# led_balloon_v28.net
KiCad netlist of a schematic drawn in EAGLE
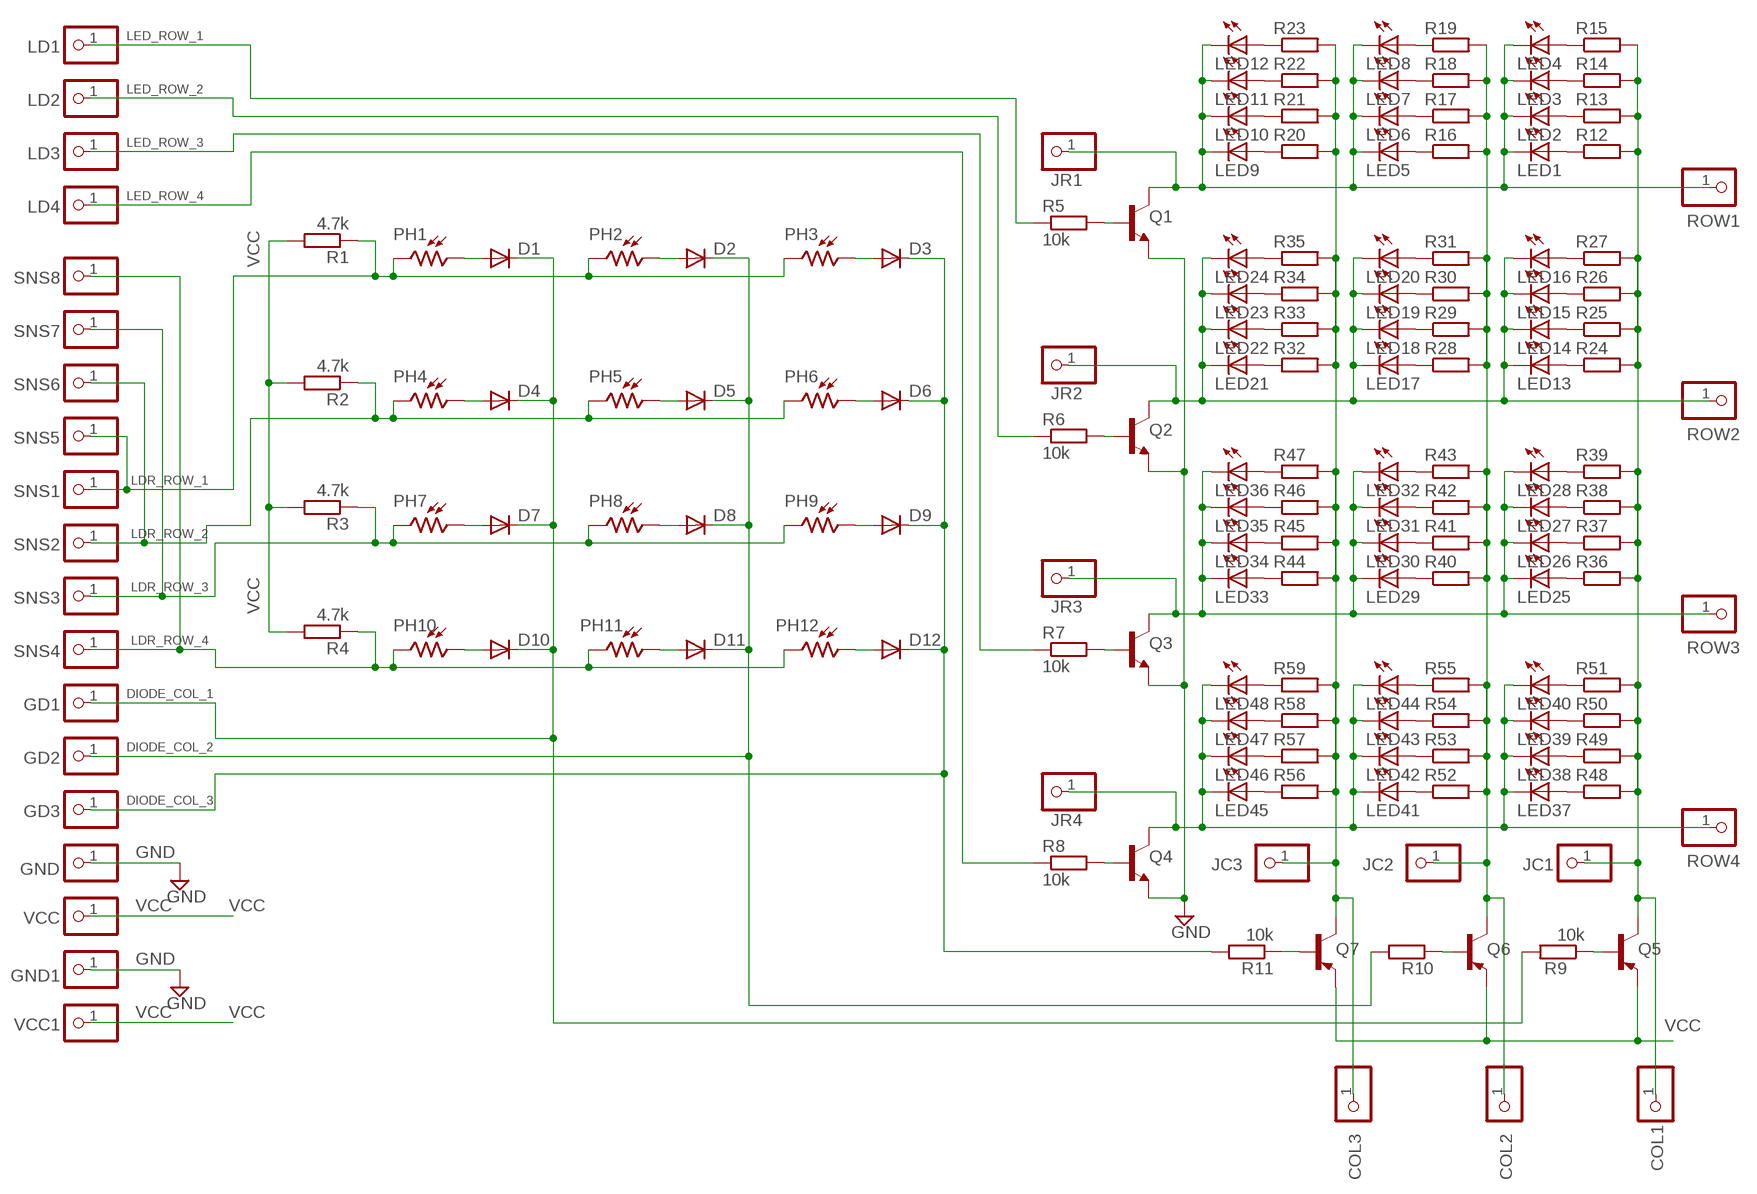
[diagram p0: schematic, sheet 1]

(export (version "E")
  (design (tool "Eeschema 10.0.6"))
  (components
    (comp (ref "COL1")
      (value "PINHD-1X1")
      (footprint "eagle-import:1X01")
      (libsource (lib "eagle-import") (part "PINHD-1X1"))
    )
    (comp (ref "COL2")
      (value "PINHD-1X1")
      (footprint "eagle-import:1X01")
      (libsource (lib "eagle-import") (part "PINHD-1X1"))
    )
    (comp (ref "COL3")
      (value "PINHD-1X1")
      (footprint "eagle-import:1X01")
      (libsource (lib "eagle-import") (part "PINHD-1X1"))
    )
    (comp (ref "D1")
      (value "1N4148DO35-7")
      (footprint "eagle-import:DO35-7")
      (libsource (lib "eagle-import") (part "1N4148DO35-7"))
    )
    (comp (ref "D2")
      (value "1N4148DO35-7")
      (footprint "eagle-import:DO35-7")
      (libsource (lib "eagle-import") (part "1N4148DO35-7"))
    )
    (comp (ref "D3")
      (value "1N4148DO35-7")
      (footprint "eagle-import:DO35-7")
      (libsource (lib "eagle-import") (part "1N4148DO35-7"))
    )
    (comp (ref "D4")
      (value "1N4148DO35-7")
      (footprint "eagle-import:DO35-7")
      (libsource (lib "eagle-import") (part "1N4148DO35-7"))
    )
    (comp (ref "D5")
      (value "1N4148DO35-7")
      (footprint "eagle-import:DO35-7")
      (libsource (lib "eagle-import") (part "1N4148DO35-7"))
    )
    (comp (ref "D6")
      (value "1N4148DO35-7")
      (footprint "eagle-import:DO35-7")
      (libsource (lib "eagle-import") (part "1N4148DO35-7"))
    )
    (comp (ref "D7")
      (value "1N4148DO35-7")
      (footprint "eagle-import:DO35-7")
      (libsource (lib "eagle-import") (part "1N4148DO35-7"))
    )
    (comp (ref "D8")
      (value "1N4148DO35-7")
      (footprint "eagle-import:DO35-7")
      (libsource (lib "eagle-import") (part "1N4148DO35-7"))
    )
    (comp (ref "D9")
      (value "1N4148DO35-7")
      (footprint "eagle-import:DO35-7")
      (libsource (lib "eagle-import") (part "1N4148DO35-7"))
    )
    (comp (ref "D10")
      (value "1N4148DO35-7")
      (footprint "eagle-import:DO35-7")
      (libsource (lib "eagle-import") (part "1N4148DO35-7"))
    )
    (comp (ref "D11")
      (value "1N4148DO35-7")
      (footprint "eagle-import:DO35-7")
      (libsource (lib "eagle-import") (part "1N4148DO35-7"))
    )
    (comp (ref "D12")
      (value "1N4148DO35-7")
      (footprint "eagle-import:DO35-7")
      (libsource (lib "eagle-import") (part "1N4148DO35-7"))
    )
    (comp (ref "GD1")
      (value "PINHD-1X1")
      (footprint "eagle-import:1X01")
      (libsource (lib "eagle-import") (part "PINHD-1X1"))
    )
    (comp (ref "GD2")
      (value "PINHD-1X1")
      (footprint "eagle-import:1X01")
      (libsource (lib "eagle-import") (part "PINHD-1X1"))
    )
    (comp (ref "GD3")
      (value "PINHD-1X1")
      (footprint "eagle-import:1X01")
      (libsource (lib "eagle-import") (part "PINHD-1X1"))
    )
    (comp (ref "GND")
      (value "PINHD-1X1")
      (footprint "eagle-import:1X01")
      (libsource (lib "eagle-import") (part "PINHD-1X1"))
    )
    (comp (ref "GND1")
      (value "PINHD-1X1")
      (footprint "eagle-import:1X01")
      (libsource (lib "eagle-import") (part "PINHD-1X1"))
    )
    (comp (ref "JC1")
      (value "PINHD-1X1")
      (footprint "eagle-import:1X01")
      (libsource (lib "eagle-import") (part "PINHD-1X1"))
    )
    (comp (ref "JC2")
      (value "PINHD-1X1")
      (footprint "eagle-import:1X01")
      (libsource (lib "eagle-import") (part "PINHD-1X1"))
    )
    (comp (ref "JC3")
      (value "PINHD-1X1")
      (footprint "eagle-import:1X01")
      (libsource (lib "eagle-import") (part "PINHD-1X1"))
    )
    (comp (ref "JR1")
      (value "PINHD-1X1")
      (footprint "eagle-import:1X01")
      (libsource (lib "eagle-import") (part "PINHD-1X1"))
    )
    (comp (ref "JR2")
      (value "PINHD-1X1")
      (footprint "eagle-import:1X01")
      (libsource (lib "eagle-import") (part "PINHD-1X1"))
    )
    (comp (ref "JR3")
      (value "PINHD-1X1")
      (footprint "eagle-import:1X01")
      (libsource (lib "eagle-import") (part "PINHD-1X1"))
    )
    (comp (ref "JR4")
      (value "PINHD-1X1")
      (footprint "eagle-import:1X01")
      (libsource (lib "eagle-import") (part "PINHD-1X1"))
    )
    (comp (ref "LD1")
      (value "PINHD-1X1")
      (footprint "eagle-import:1X01")
      (libsource (lib "eagle-import") (part "PINHD-1X1"))
    )
    (comp (ref "LD2")
      (value "PINHD-1X1")
      (footprint "eagle-import:1X01")
      (libsource (lib "eagle-import") (part "PINHD-1X1"))
    )
    (comp (ref "LD3")
      (value "PINHD-1X1")
      (footprint "eagle-import:1X01")
      (libsource (lib "eagle-import") (part "PINHD-1X1"))
    )
    (comp (ref "LD4")
      (value "PINHD-1X1")
      (footprint "eagle-import:1X01")
      (libsource (lib "eagle-import") (part "PINHD-1X1"))
    )
    (comp (ref "LED1")
      (value "LED3MM")
      (footprint "eagle-import:LED3MM")
      (libsource (lib "eagle-import") (part "LED3MM"))
    )
    (comp (ref "LED2")
      (value "LED3MM")
      (footprint "eagle-import:LED3MM")
      (libsource (lib "eagle-import") (part "LED3MM"))
    )
    (comp (ref "LED3")
      (value "LED3MM")
      (footprint "eagle-import:LED3MM")
      (libsource (lib "eagle-import") (part "LED3MM"))
    )
    (comp (ref "LED4")
      (value "LED3MM")
      (footprint "eagle-import:LED3MM")
      (libsource (lib "eagle-import") (part "LED3MM"))
    )
    (comp (ref "LED5")
      (value "LED3MM")
      (footprint "eagle-import:LED3MM")
      (libsource (lib "eagle-import") (part "LED3MM"))
    )
    (comp (ref "LED6")
      (value "LED3MM")
      (footprint "eagle-import:LED3MM")
      (libsource (lib "eagle-import") (part "LED3MM"))
    )
    (comp (ref "LED7")
      (value "LED3MM")
      (footprint "eagle-import:LED3MM")
      (libsource (lib "eagle-import") (part "LED3MM"))
    )
    (comp (ref "LED8")
      (value "LED3MM")
      (footprint "eagle-import:LED3MM")
      (libsource (lib "eagle-import") (part "LED3MM"))
    )
    (comp (ref "LED9")
      (value "LED3MM")
      (footprint "eagle-import:LED3MM")
      (libsource (lib "eagle-import") (part "LED3MM"))
    )
    (comp (ref "LED10")
      (value "LED3MM")
      (footprint "eagle-import:LED3MM")
      (libsource (lib "eagle-import") (part "LED3MM"))
    )
    (comp (ref "LED11")
      (value "LED3MM")
      (footprint "eagle-import:LED3MM")
      (libsource (lib "eagle-import") (part "LED3MM"))
    )
    (comp (ref "LED12")
      (value "LED3MM")
      (footprint "eagle-import:LED3MM")
      (libsource (lib "eagle-import") (part "LED3MM"))
    )
    (comp (ref "LED13")
      (value "LED3MM")
      (footprint "eagle-import:LED3MM")
      (libsource (lib "eagle-import") (part "LED3MM"))
    )
    (comp (ref "LED14")
      (value "LED3MM")
      (footprint "eagle-import:LED3MM")
      (libsource (lib "eagle-import") (part "LED3MM"))
    )
    (comp (ref "LED15")
      (value "LED3MM")
      (footprint "eagle-import:LED3MM")
      (libsource (lib "eagle-import") (part "LED3MM"))
    )
    (comp (ref "LED16")
      (value "LED3MM")
      (footprint "eagle-import:LED3MM")
      (libsource (lib "eagle-import") (part "LED3MM"))
    )
    (comp (ref "LED17")
      (value "LED3MM")
      (footprint "eagle-import:LED3MM")
      (libsource (lib "eagle-import") (part "LED3MM"))
    )
    (comp (ref "LED18")
      (value "LED3MM")
      (footprint "eagle-import:LED3MM")
      (libsource (lib "eagle-import") (part "LED3MM"))
    )
    (comp (ref "LED19")
      (value "LED3MM")
      (footprint "eagle-import:LED3MM")
      (libsource (lib "eagle-import") (part "LED3MM"))
    )
    (comp (ref "LED20")
      (value "LED3MM")
      (footprint "eagle-import:LED3MM")
      (libsource (lib "eagle-import") (part "LED3MM"))
    )
    (comp (ref "LED21")
      (value "LED3MM")
      (footprint "eagle-import:LED3MM")
      (libsource (lib "eagle-import") (part "LED3MM"))
    )
    (comp (ref "LED22")
      (value "LED3MM")
      (footprint "eagle-import:LED3MM")
      (libsource (lib "eagle-import") (part "LED3MM"))
    )
    (comp (ref "LED23")
      (value "LED3MM")
      (footprint "eagle-import:LED3MM")
      (libsource (lib "eagle-import") (part "LED3MM"))
    )
    (comp (ref "LED24")
      (value "LED3MM")
      (footprint "eagle-import:LED3MM")
      (libsource (lib "eagle-import") (part "LED3MM"))
    )
    (comp (ref "LED25")
      (value "LED3MM")
      (footprint "eagle-import:LED3MM")
      (libsource (lib "eagle-import") (part "LED3MM"))
    )
    (comp (ref "LED26")
      (value "LED3MM")
      (footprint "eagle-import:LED3MM")
      (libsource (lib "eagle-import") (part "LED3MM"))
    )
    (comp (ref "LED27")
      (value "LED3MM")
      (footprint "eagle-import:LED3MM")
      (libsource (lib "eagle-import") (part "LED3MM"))
    )
    (comp (ref "LED28")
      (value "LED3MM")
      (footprint "eagle-import:LED3MM")
      (libsource (lib "eagle-import") (part "LED3MM"))
    )
    (comp (ref "LED29")
      (value "LED3MM")
      (footprint "eagle-import:LED3MM")
      (libsource (lib "eagle-import") (part "LED3MM"))
    )
    (comp (ref "LED30")
      (value "LED3MM")
      (footprint "eagle-import:LED3MM")
      (libsource (lib "eagle-import") (part "LED3MM"))
    )
    (comp (ref "LED31")
      (value "LED3MM")
      (footprint "eagle-import:LED3MM")
      (libsource (lib "eagle-import") (part "LED3MM"))
    )
    (comp (ref "LED32")
      (value "LED3MM")
      (footprint "eagle-import:LED3MM")
      (libsource (lib "eagle-import") (part "LED3MM"))
    )
    (comp (ref "LED33")
      (value "LED3MM")
      (footprint "eagle-import:LED3MM")
      (libsource (lib "eagle-import") (part "LED3MM"))
    )
    (comp (ref "LED34")
      (value "LED3MM")
      (footprint "eagle-import:LED3MM")
      (libsource (lib "eagle-import") (part "LED3MM"))
    )
    (comp (ref "LED35")
      (value "LED3MM")
      (footprint "eagle-import:LED3MM")
      (libsource (lib "eagle-import") (part "LED3MM"))
    )
    (comp (ref "LED36")
      (value "LED3MM")
      (footprint "eagle-import:LED3MM")
      (libsource (lib "eagle-import") (part "LED3MM"))
    )
    (comp (ref "LED37")
      (value "LED3MM")
      (footprint "eagle-import:LED3MM")
      (libsource (lib "eagle-import") (part "LED3MM"))
    )
    (comp (ref "LED38")
      (value "LED3MM")
      (footprint "eagle-import:LED3MM")
      (libsource (lib "eagle-import") (part "LED3MM"))
    )
    (comp (ref "LED39")
      (value "LED3MM")
      (footprint "eagle-import:LED3MM")
      (libsource (lib "eagle-import") (part "LED3MM"))
    )
    (comp (ref "LED40")
      (value "LED3MM")
      (footprint "eagle-import:LED3MM")
      (libsource (lib "eagle-import") (part "LED3MM"))
    )
    (comp (ref "LED41")
      (value "LED3MM")
      (footprint "eagle-import:LED3MM")
      (libsource (lib "eagle-import") (part "LED3MM"))
    )
    (comp (ref "LED42")
      (value "LED3MM")
      (footprint "eagle-import:LED3MM")
      (libsource (lib "eagle-import") (part "LED3MM"))
    )
    (comp (ref "LED43")
      (value "LED3MM")
      (footprint "eagle-import:LED3MM")
      (libsource (lib "eagle-import") (part "LED3MM"))
    )
    (comp (ref "LED44")
      (value "LED3MM")
      (footprint "eagle-import:LED3MM")
      (libsource (lib "eagle-import") (part "LED3MM"))
    )
    (comp (ref "LED45")
      (value "LED3MM")
      (footprint "eagle-import:LED3MM")
      (libsource (lib "eagle-import") (part "LED3MM"))
    )
    (comp (ref "LED46")
      (value "LED3MM")
      (footprint "eagle-import:LED3MM")
      (libsource (lib "eagle-import") (part "LED3MM"))
    )
    (comp (ref "LED47")
      (value "LED3MM")
      (footprint "eagle-import:LED3MM")
      (libsource (lib "eagle-import") (part "LED3MM"))
    )
    (comp (ref "LED48")
      (value "LED3MM")
      (footprint "eagle-import:LED3MM")
      (libsource (lib "eagle-import") (part "LED3MM"))
    )
    (comp (ref "PH1")
      (value "LDR")
      (footprint "eagle-import:VT900")
      (libsource (lib "eagle-import") (part "LDR"))
    )
    (comp (ref "PH2")
      (value "VT83N4")
      (footprint "eagle-import:VT800")
      (libsource (lib "eagle-import") (part "VT83N4"))
    )
    (comp (ref "PH3")
      (value "VT83N4")
      (footprint "eagle-import:VT800")
      (libsource (lib "eagle-import") (part "VT83N4"))
    )
    (comp (ref "PH4")
      (value "VT83N4")
      (footprint "eagle-import:VT800")
      (libsource (lib "eagle-import") (part "VT83N4"))
    )
    (comp (ref "PH5")
      (value "VT83N4")
      (footprint "eagle-import:VT800")
      (libsource (lib "eagle-import") (part "VT83N4"))
    )
    (comp (ref "PH6")
      (value "VT83N4")
      (footprint "eagle-import:VT800")
      (libsource (lib "eagle-import") (part "VT83N4"))
    )
    (comp (ref "PH7")
      (value "VT83N4")
      (footprint "eagle-import:VT800")
      (libsource (lib "eagle-import") (part "VT83N4"))
    )
    (comp (ref "PH8")
      (value "VT83N4")
      (footprint "eagle-import:VT800")
      (libsource (lib "eagle-import") (part "VT83N4"))
    )
    (comp (ref "PH9")
      (value "VT83N4")
      (footprint "eagle-import:VT800")
      (libsource (lib "eagle-import") (part "VT83N4"))
    )
    (comp (ref "PH10")
      (value "VT83N4")
      (footprint "eagle-import:VT800")
      (libsource (lib "eagle-import") (part "VT83N4"))
    )
    (comp (ref "PH11")
      (value "VT83N4")
      (footprint "eagle-import:VT800")
      (libsource (lib "eagle-import") (part "VT83N4"))
    )
    (comp (ref "PH12")
      (value "VT83N4")
      (footprint "eagle-import:VT800")
      (libsource (lib "eagle-import") (part "VT83N4"))
    )
    (comp (ref "Q1")
      (value "BC847ASMD")
      (footprint "eagle-import:SOT23")
      (libsource (lib "eagle-import") (part "BC847SMDA"))
    )
    (comp (ref "Q2")
      (value "BC847ASMD")
      (footprint "eagle-import:SOT23")
      (libsource (lib "eagle-import") (part "BC847SMDA"))
    )
    (comp (ref "Q3")
      (value "BC847ASMD")
      (footprint "eagle-import:SOT23")
      (libsource (lib "eagle-import") (part "BC847SMDA"))
    )
    (comp (ref "Q4")
      (value "BC847ASMD")
      (footprint "eagle-import:SOT23")
      (libsource (lib "eagle-import") (part "BC847SMDA"))
    )
    (comp (ref "Q5")
      (value "BC807-40SMD")
      (footprint "eagle-import:SOT23-BEC")
      (libsource (lib "eagle-import") (part "BC807SMD-40"))
    )
    (comp (ref "Q6")
      (value "BC807-40SMD")
      (footprint "eagle-import:SOT23-BEC")
      (libsource (lib "eagle-import") (part "BC807SMD-40"))
    )
    (comp (ref "Q7")
      (value "BC807-40SMD")
      (footprint "eagle-import:SOT23-BEC")
      (libsource (lib "eagle-import") (part "BC807SMD-40"))
    )
    (comp (ref "R1")
      (value "4.7k")
      (footprint "eagle-import:0204_5")
      (libsource (lib "eagle-import") (part "resistor_R-EU_0204/5"))
    )
    (comp (ref "R2")
      (value "4.7k")
      (footprint "eagle-import:0204_5")
      (libsource (lib "eagle-import") (part "resistor_R-EU_0204/5"))
    )
    (comp (ref "R3")
      (value "4.7k")
      (footprint "eagle-import:0204_5")
      (libsource (lib "eagle-import") (part "resistor_R-EU_0204/5"))
    )
    (comp (ref "R4")
      (value "4.7k")
      (footprint "eagle-import:0204_5")
      (libsource (lib "eagle-import") (part "resistor_R-EU_0204/5"))
    )
    (comp (ref "R5")
      (value "10k")
      (footprint "eagle-import:0204_5")
      (libsource (lib "eagle-import") (part "resistor_R-EU_0204/5"))
    )
    (comp (ref "R6")
      (value "10k")
      (footprint "eagle-import:0204_5")
      (libsource (lib "eagle-import") (part "resistor_R-EU_0204/5"))
    )
    (comp (ref "R7")
      (value "10k")
      (footprint "eagle-import:0204_5")
      (libsource (lib "eagle-import") (part "resistor_R-EU_0204/5"))
    )
    (comp (ref "R8")
      (value "10k")
      (footprint "eagle-import:0204_5")
      (libsource (lib "eagle-import") (part "resistor_R-EU_0204/5"))
    )
    (comp (ref "R9")
      (value "10k")
      (footprint "eagle-import:0204_5")
      (libsource (lib "eagle-import") (part "resistor_R-EU_0204/5"))
    )
    (comp (ref "R10")
      (value "10k")
      (footprint "eagle-import:0204_5")
      (libsource (lib "eagle-import") (part "resistor_R-EU_0204/5"))
    )
    (comp (ref "R11")
      (value "10k")
      (footprint "eagle-import:0204_5")
      (libsource (lib "eagle-import") (part "resistor_R-EU_0204/5"))
    )
    (comp (ref "R12")
      (value "R-EU_R0805")
      (footprint "eagle-import:R0805")
      (libsource (lib "eagle-import") (part "R-EU_R0805"))
    )
    (comp (ref "R13")
      (value "R-EU_R0805")
      (footprint "eagle-import:R0805")
      (libsource (lib "eagle-import") (part "R-EU_R0805"))
    )
    (comp (ref "R14")
      (value "R-EU_R0805")
      (footprint "eagle-import:R0805")
      (libsource (lib "eagle-import") (part "R-EU_R0805"))
    )
    (comp (ref "R15")
      (value "R-EU_R0805")
      (footprint "eagle-import:R0805")
      (libsource (lib "eagle-import") (part "R-EU_R0805"))
    )
    (comp (ref "R16")
      (value "R-EU_R0805")
      (footprint "eagle-import:R0805")
      (libsource (lib "eagle-import") (part "R-EU_R0805"))
    )
    (comp (ref "R17")
      (value "R-EU_R0805")
      (footprint "eagle-import:R0805")
      (libsource (lib "eagle-import") (part "R-EU_R0805"))
    )
    (comp (ref "R18")
      (value "R-EU_R0805")
      (footprint "eagle-import:R0805")
      (libsource (lib "eagle-import") (part "R-EU_R0805"))
    )
    (comp (ref "R19")
      (value "R-EU_R0805")
      (footprint "eagle-import:R0805")
      (libsource (lib "eagle-import") (part "R-EU_R0805"))
    )
    (comp (ref "R20")
      (value "R-EU_R0805")
      (footprint "eagle-import:R0805")
      (libsource (lib "eagle-import") (part "R-EU_R0805"))
    )
    (comp (ref "R21")
      (value "R-EU_R0805")
      (footprint "eagle-import:R0805")
      (libsource (lib "eagle-import") (part "R-EU_R0805"))
    )
    (comp (ref "R22")
      (value "R-EU_R0805")
      (footprint "eagle-import:R0805")
      (libsource (lib "eagle-import") (part "R-EU_R0805"))
    )
    (comp (ref "R23")
      (value "R-EU_R0805")
      (footprint "eagle-import:R0805")
      (libsource (lib "eagle-import") (part "R-EU_R0805"))
    )
    (comp (ref "R24")
      (value "R-EU_R0805")
      (footprint "eagle-import:R0805")
      (libsource (lib "eagle-import") (part "R-EU_R0805"))
    )
    (comp (ref "R25")
      (value "R-EU_R0805")
      (footprint "eagle-import:R0805")
      (libsource (lib "eagle-import") (part "R-EU_R0805"))
    )
    (comp (ref "R26")
      (value "R-EU_R0805")
      (footprint "eagle-import:R0805")
      (libsource (lib "eagle-import") (part "R-EU_R0805"))
    )
    (comp (ref "R27")
      (value "R-EU_R0805")
      (footprint "eagle-import:R0805")
      (libsource (lib "eagle-import") (part "R-EU_R0805"))
    )
    (comp (ref "R28")
      (value "R-EU_R0805")
      (footprint "eagle-import:R0805")
      (libsource (lib "eagle-import") (part "R-EU_R0805"))
    )
    (comp (ref "R29")
      (value "R-EU_R0805")
      (footprint "eagle-import:R0805")
      (libsource (lib "eagle-import") (part "R-EU_R0805"))
    )
    (comp (ref "R30")
      (value "R-EU_R0805")
      (footprint "eagle-import:R0805")
      (libsource (lib "eagle-import") (part "R-EU_R0805"))
    )
    (comp (ref "R31")
      (value "R-EU_R0805")
      (footprint "eagle-import:R0805")
      (libsource (lib "eagle-import") (part "R-EU_R0805"))
    )
    (comp (ref "R32")
      (value "R-EU_R0805")
      (footprint "eagle-import:R0805")
      (libsource (lib "eagle-import") (part "R-EU_R0805"))
    )
    (comp (ref "R33")
      (value "R-EU_R0805")
      (footprint "eagle-import:R0805")
      (libsource (lib "eagle-import") (part "R-EU_R0805"))
    )
    (comp (ref "R34")
      (value "R-EU_R0805")
      (footprint "eagle-import:R0805")
      (libsource (lib "eagle-import") (part "R-EU_R0805"))
    )
    (comp (ref "R35")
      (value "R-EU_R0805")
      (footprint "eagle-import:R0805")
      (libsource (lib "eagle-import") (part "R-EU_R0805"))
    )
    (comp (ref "R36")
      (value "R-EU_R0805")
      (footprint "eagle-import:R0805")
      (libsource (lib "eagle-import") (part "R-EU_R0805"))
    )
    (comp (ref "R37")
      (value "R-EU_R0805")
      (footprint "eagle-import:R0805")
      (libsource (lib "eagle-import") (part "R-EU_R0805"))
    )
    (comp (ref "R38")
      (value "R-EU_R0805")
      (footprint "eagle-import:R0805")
      (libsource (lib "eagle-import") (part "R-EU_R0805"))
    )
    (comp (ref "R39")
      (value "R-EU_R0805")
      (footprint "eagle-import:R0805")
      (libsource (lib "eagle-import") (part "R-EU_R0805"))
    )
    (comp (ref "R40")
      (value "R-EU_R0805")
      (footprint "eagle-import:R0805")
      (libsource (lib "eagle-import") (part "R-EU_R0805"))
    )
    (comp (ref "R41")
      (value "R-EU_R0805")
      (footprint "eagle-import:R0805")
      (libsource (lib "eagle-import") (part "R-EU_R0805"))
    )
    (comp (ref "R42")
      (value "R-EU_R0805")
      (footprint "eagle-import:R0805")
      (libsource (lib "eagle-import") (part "R-EU_R0805"))
    )
    (comp (ref "R43")
      (value "R-EU_R0805")
      (footprint "eagle-import:R0805")
      (libsource (lib "eagle-import") (part "R-EU_R0805"))
    )
    (comp (ref "R44")
      (value "R-EU_R0805")
      (footprint "eagle-import:R0805")
      (libsource (lib "eagle-import") (part "R-EU_R0805"))
    )
    (comp (ref "R45")
      (value "R-EU_R0805")
      (footprint "eagle-import:R0805")
      (libsource (lib "eagle-import") (part "R-EU_R0805"))
    )
    (comp (ref "R46")
      (value "R-EU_R0805")
      (footprint "eagle-import:R0805")
      (libsource (lib "eagle-import") (part "R-EU_R0805"))
    )
    (comp (ref "R47")
      (value "R-EU_R0805")
      (footprint "eagle-import:R0805")
      (libsource (lib "eagle-import") (part "R-EU_R0805"))
    )
    (comp (ref "R48")
      (value "R-EU_R0805")
      (footprint "eagle-import:R0805")
      (libsource (lib "eagle-import") (part "R-EU_R0805"))
    )
    (comp (ref "R49")
      (value "R-EU_R0805")
      (footprint "eagle-import:R0805")
      (libsource (lib "eagle-import") (part "R-EU_R0805"))
    )
    (comp (ref "R50")
      (value "R-EU_R0805")
      (footprint "eagle-import:R0805")
      (libsource (lib "eagle-import") (part "R-EU_R0805"))
    )
    (comp (ref "R51")
      (value "R-EU_R0805")
      (footprint "eagle-import:R0805")
      (libsource (lib "eagle-import") (part "R-EU_R0805"))
    )
    (comp (ref "R52")
      (value "R-EU_R0805")
      (footprint "eagle-import:R0805")
      (libsource (lib "eagle-import") (part "R-EU_R0805"))
    )
    (comp (ref "R53")
      (value "R-EU_R0805")
      (footprint "eagle-import:R0805")
      (libsource (lib "eagle-import") (part "R-EU_R0805"))
    )
    (comp (ref "R54")
      (value "R-EU_R0805")
      (footprint "eagle-import:R0805")
      (libsource (lib "eagle-import") (part "R-EU_R0805"))
    )
    (comp (ref "R55")
      (value "R-EU_R0805")
      (footprint "eagle-import:R0805")
      (libsource (lib "eagle-import") (part "R-EU_R0805"))
    )
    (comp (ref "R56")
      (value "R-EU_R0805")
      (footprint "eagle-import:R0805")
      (libsource (lib "eagle-import") (part "R-EU_R0805"))
    )
    (comp (ref "R57")
      (value "R-EU_R0805")
      (footprint "eagle-import:R0805")
      (libsource (lib "eagle-import") (part "R-EU_R0805"))
    )
    (comp (ref "R58")
      (value "R-EU_R0805")
      (footprint "eagle-import:R0805")
      (libsource (lib "eagle-import") (part "R-EU_R0805"))
    )
    (comp (ref "R59")
      (value "R-EU_R0805")
      (footprint "eagle-import:R0805")
      (libsource (lib "eagle-import") (part "R-EU_R0805"))
    )
    (comp (ref "ROW1")
      (value "PINHD-1X1")
      (footprint "eagle-import:1X01")
      (libsource (lib "eagle-import") (part "PINHD-1X1"))
    )
    (comp (ref "ROW2")
      (value "PINHD-1X1")
      (footprint "eagle-import:1X01")
      (libsource (lib "eagle-import") (part "PINHD-1X1"))
    )
    (comp (ref "ROW3")
      (value "PINHD-1X1")
      (footprint "eagle-import:1X01")
      (libsource (lib "eagle-import") (part "PINHD-1X1"))
    )
    (comp (ref "ROW4")
      (value "PINHD-1X1")
      (footprint "eagle-import:1X01")
      (libsource (lib "eagle-import") (part "PINHD-1X1"))
    )
    (comp (ref "SNS1")
      (value "PINHD-1X1")
      (footprint "eagle-import:1X01")
      (libsource (lib "eagle-import") (part "PINHD-1X1"))
    )
    (comp (ref "SNS2")
      (value "PINHD-1X1")
      (footprint "eagle-import:1X01")
      (libsource (lib "eagle-import") (part "PINHD-1X1"))
    )
    (comp (ref "SNS3")
      (value "PINHD-1X1")
      (footprint "eagle-import:1X01")
      (libsource (lib "eagle-import") (part "PINHD-1X1"))
    )
    (comp (ref "SNS4")
      (value "PINHD-1X1")
      (footprint "eagle-import:1X01")
      (libsource (lib "eagle-import") (part "PINHD-1X1"))
    )
    (comp (ref "SNS5")
      (value "PINHD-1X1")
      (footprint "eagle-import:1X01")
      (libsource (lib "eagle-import") (part "PINHD-1X1"))
    )
    (comp (ref "SNS6")
      (value "PINHD-1X1")
      (footprint "eagle-import:1X01")
      (libsource (lib "eagle-import") (part "PINHD-1X1"))
    )
    (comp (ref "SNS7")
      (value "PINHD-1X1")
      (footprint "eagle-import:1X01")
      (libsource (lib "eagle-import") (part "PINHD-1X1"))
    )
    (comp (ref "SNS8")
      (value "PINHD-1X1")
      (footprint "eagle-import:1X01")
      (libsource (lib "eagle-import") (part "PINHD-1X1"))
    )
    (comp (ref "VCC")
      (value "PINHD-1X1")
      (footprint "eagle-import:1X01")
      (libsource (lib "eagle-import") (part "PINHD-1X1"))
    )
    (comp (ref "VCC1")
      (value "PINHD-1X1")
      (footprint "eagle-import:1X01")
      (libsource (lib "eagle-import") (part "PINHD-1X1"))
    )
  )
  (nets
    (net (code "1") (name "/DIODE_COL_1") (class "Default")
      (node (ref "D1") (pin "C") (pinfunction "C_C") (pintype "passive"))
      (node (ref "D10") (pin "C") (pinfunction "C_C") (pintype "passive"))
      (node (ref "D4") (pin "C") (pinfunction "C_C") (pintype "passive"))
      (node (ref "D7") (pin "C") (pinfunction "C_C") (pintype "passive"))
      (node (ref "GD1") (pin "1") (pinfunction "1_1") (pintype "passive"))
      (node (ref "R9") (pin "2") (pinfunction "2_2") (pintype "passive"))
    )
    (net (code "2") (name "/DIODE_COL_2") (class "Default")
      (node (ref "D11") (pin "C") (pinfunction "C_C") (pintype "passive"))
      (node (ref "D2") (pin "C") (pinfunction "C_C") (pintype "passive"))
      (node (ref "D5") (pin "C") (pinfunction "C_C") (pintype "passive"))
      (node (ref "D8") (pin "C") (pinfunction "C_C") (pintype "passive"))
      (node (ref "GD2") (pin "1") (pinfunction "1_1") (pintype "passive"))
      (node (ref "R10") (pin "2") (pinfunction "2_2") (pintype "passive"))
    )
    (net (code "3") (name "/DIODE_COL_3") (class "Default")
      (node (ref "D12") (pin "C") (pinfunction "C_C") (pintype "passive"))
      (node (ref "D3") (pin "C") (pinfunction "C_C") (pintype "passive"))
      (node (ref "D6") (pin "C") (pinfunction "C_C") (pintype "passive"))
      (node (ref "D9") (pin "C") (pinfunction "C_C") (pintype "passive"))
      (node (ref "GD3") (pin "1") (pinfunction "1_1") (pintype "passive"))
      (node (ref "R11") (pin "2") (pinfunction "2_2") (pintype "passive"))
    )
    (net (code "4") (name "/LDR_ROW_1") (class "Default")
      (node (ref "PH1") (pin "2") (pinfunction "2_2") (pintype "passive"))
      (node (ref "PH2") (pin "2") (pinfunction "2_2") (pintype "passive"))
      (node (ref "PH3") (pin "2") (pinfunction "2_2") (pintype "passive"))
      (node (ref "R1") (pin "1") (pinfunction "1_1") (pintype "passive"))
      (node (ref "SNS1") (pin "1") (pinfunction "1_1") (pintype "passive"))
      (node (ref "SNS5") (pin "1") (pinfunction "1_1") (pintype "passive"))
    )
    (net (code "5") (name "/LDR_ROW_2") (class "Default")
      (node (ref "PH4") (pin "2") (pinfunction "2_2") (pintype "passive"))
      (node (ref "PH5") (pin "2") (pinfunction "2_2") (pintype "passive"))
      (node (ref "PH6") (pin "2") (pinfunction "2_2") (pintype "passive"))
      (node (ref "R2") (pin "1") (pinfunction "1_1") (pintype "passive"))
      (node (ref "SNS2") (pin "1") (pinfunction "1_1") (pintype "passive"))
      (node (ref "SNS6") (pin "1") (pinfunction "1_1") (pintype "passive"))
    )
    (net (code "6") (name "/LDR_ROW_3") (class "Default")
      (node (ref "PH7") (pin "2") (pinfunction "2_2") (pintype "passive"))
      (node (ref "PH8") (pin "2") (pinfunction "2_2") (pintype "passive"))
      (node (ref "PH9") (pin "2") (pinfunction "2_2") (pintype "passive"))
      (node (ref "R3") (pin "1") (pinfunction "1_1") (pintype "passive"))
      (node (ref "SNS3") (pin "1") (pinfunction "1_1") (pintype "passive"))
      (node (ref "SNS7") (pin "1") (pinfunction "1_1") (pintype "passive"))
    )
    (net (code "7") (name "/LDR_ROW_4") (class "Default")
      (node (ref "PH10") (pin "2") (pinfunction "2_2") (pintype "passive"))
      (node (ref "PH11") (pin "2") (pinfunction "2_2") (pintype "passive"))
      (node (ref "PH12") (pin "2") (pinfunction "2_2") (pintype "passive"))
      (node (ref "R4") (pin "1") (pinfunction "1_1") (pintype "passive"))
      (node (ref "SNS4") (pin "1") (pinfunction "1_1") (pintype "passive"))
      (node (ref "SNS8") (pin "1") (pinfunction "1_1") (pintype "passive"))
    )
    (net (code "8") (name "/LED_ROW_1") (class "Default")
      (node (ref "LD1") (pin "1") (pinfunction "1_1") (pintype "passive"))
      (node (ref "R5") (pin "1") (pinfunction "1_1") (pintype "passive"))
    )
    (net (code "9") (name "/LED_ROW_2") (class "Default")
      (node (ref "LD2") (pin "1") (pinfunction "1_1") (pintype "passive"))
      (node (ref "R6") (pin "1") (pinfunction "1_1") (pintype "passive"))
    )
    (net (code "10") (name "/LED_ROW_3") (class "Default")
      (node (ref "LD3") (pin "1") (pinfunction "1_1") (pintype "passive"))
      (node (ref "R7") (pin "1") (pinfunction "1_1") (pintype "passive"))
    )
    (net (code "11") (name "/LED_ROW_4") (class "Default")
      (node (ref "LD4") (pin "1") (pinfunction "1_1") (pintype "passive"))
      (node (ref "R8") (pin "1") (pinfunction "1_1") (pintype "passive"))
    )
    (net (code "12") (name "/VCC") (class "Default")
      (node (ref "Q5") (pin "E") (pinfunction "E_E") (pintype "passive"))
      (node (ref "Q6") (pin "E") (pinfunction "E_E") (pintype "passive"))
      (node (ref "Q7") (pin "E") (pinfunction "E_E") (pintype "passive"))
      (node (ref "R1") (pin "2") (pinfunction "2_2") (pintype "passive"))
      (node (ref "R2") (pin "2") (pinfunction "2_2") (pintype "passive"))
      (node (ref "R3") (pin "2") (pinfunction "2_2") (pintype "passive"))
      (node (ref "R4") (pin "2") (pinfunction "2_2") (pintype "passive"))
      (node (ref "VCC") (pin "1") (pinfunction "1_1") (pintype "passive"))
      (node (ref "VCC1") (pin "1") (pinfunction "1_1") (pintype "passive"))
    )
    (net (code "13") (name "GND") (class "Default")
      (node (ref "GND") (pin "1") (pinfunction "1_1") (pintype "passive"))
      (node (ref "GND1") (pin "1") (pinfunction "1_1") (pintype "passive"))
      (node (ref "Q1") (pin "2") (pinfunction "E_2") (pintype "passive"))
      (node (ref "Q2") (pin "2") (pinfunction "E_2") (pintype "passive"))
      (node (ref "Q3") (pin "2") (pinfunction "E_2") (pintype "passive"))
      (node (ref "Q4") (pin "2") (pinfunction "E_2") (pintype "passive"))
    )
    (net (code "14") (name "Net-(COL1-Pad1)") (class "Default")
      (node (ref "COL1") (pin "1") (pinfunction "1_1") (pintype "passive"))
      (node (ref "JC1") (pin "1") (pinfunction "1_1") (pintype "passive"))
      (node (ref "Q5") (pin "C") (pinfunction "C_C") (pintype "passive"))
      (node (ref "R12") (pin "2") (pinfunction "2_2") (pintype "passive"))
      (node (ref "R13") (pin "2") (pinfunction "2_2") (pintype "passive"))
      (node (ref "R14") (pin "2") (pinfunction "2_2") (pintype "passive"))
      (node (ref "R15") (pin "2") (pinfunction "2_2") (pintype "passive"))
      (node (ref "R24") (pin "2") (pinfunction "2_2") (pintype "passive"))
      (node (ref "R25") (pin "2") (pinfunction "2_2") (pintype "passive"))
      (node (ref "R26") (pin "2") (pinfunction "2_2") (pintype "passive"))
      (node (ref "R27") (pin "2") (pinfunction "2_2") (pintype "passive"))
      (node (ref "R36") (pin "2") (pinfunction "2_2") (pintype "passive"))
      (node (ref "R37") (pin "2") (pinfunction "2_2") (pintype "passive"))
      (node (ref "R38") (pin "2") (pinfunction "2_2") (pintype "passive"))
      (node (ref "R39") (pin "2") (pinfunction "2_2") (pintype "passive"))
      (node (ref "R48") (pin "2") (pinfunction "2_2") (pintype "passive"))
      (node (ref "R49") (pin "2") (pinfunction "2_2") (pintype "passive"))
      (node (ref "R50") (pin "2") (pinfunction "2_2") (pintype "passive"))
      (node (ref "R51") (pin "2") (pinfunction "2_2") (pintype "passive"))
    )
    (net (code "15") (name "Net-(COL2-Pad1)") (class "Default")
      (node (ref "COL2") (pin "1") (pinfunction "1_1") (pintype "passive"))
      (node (ref "JC2") (pin "1") (pinfunction "1_1") (pintype "passive"))
      (node (ref "Q6") (pin "C") (pinfunction "C_C") (pintype "passive"))
      (node (ref "R16") (pin "2") (pinfunction "2_2") (pintype "passive"))
      (node (ref "R17") (pin "2") (pinfunction "2_2") (pintype "passive"))
      (node (ref "R18") (pin "2") (pinfunction "2_2") (pintype "passive"))
      (node (ref "R19") (pin "2") (pinfunction "2_2") (pintype "passive"))
      (node (ref "R28") (pin "2") (pinfunction "2_2") (pintype "passive"))
      (node (ref "R29") (pin "2") (pinfunction "2_2") (pintype "passive"))
      (node (ref "R30") (pin "2") (pinfunction "2_2") (pintype "passive"))
      (node (ref "R31") (pin "2") (pinfunction "2_2") (pintype "passive"))
      (node (ref "R40") (pin "2") (pinfunction "2_2") (pintype "passive"))
      (node (ref "R41") (pin "2") (pinfunction "2_2") (pintype "passive"))
      (node (ref "R42") (pin "2") (pinfunction "2_2") (pintype "passive"))
      (node (ref "R43") (pin "2") (pinfunction "2_2") (pintype "passive"))
      (node (ref "R52") (pin "2") (pinfunction "2_2") (pintype "passive"))
      (node (ref "R53") (pin "2") (pinfunction "2_2") (pintype "passive"))
      (node (ref "R54") (pin "2") (pinfunction "2_2") (pintype "passive"))
      (node (ref "R55") (pin "2") (pinfunction "2_2") (pintype "passive"))
    )
    (net (code "16") (name "Net-(COL3-Pad1)") (class "Default")
      (node (ref "COL3") (pin "1") (pinfunction "1_1") (pintype "passive"))
      (node (ref "JC3") (pin "1") (pinfunction "1_1") (pintype "passive"))
      (node (ref "Q7") (pin "C") (pinfunction "C_C") (pintype "passive"))
      (node (ref "R20") (pin "2") (pinfunction "2_2") (pintype "passive"))
      (node (ref "R21") (pin "2") (pinfunction "2_2") (pintype "passive"))
      (node (ref "R22") (pin "2") (pinfunction "2_2") (pintype "passive"))
      (node (ref "R23") (pin "2") (pinfunction "2_2") (pintype "passive"))
      (node (ref "R32") (pin "2") (pinfunction "2_2") (pintype "passive"))
      (node (ref "R33") (pin "2") (pinfunction "2_2") (pintype "passive"))
      (node (ref "R34") (pin "2") (pinfunction "2_2") (pintype "passive"))
      (node (ref "R35") (pin "2") (pinfunction "2_2") (pintype "passive"))
      (node (ref "R44") (pin "2") (pinfunction "2_2") (pintype "passive"))
      (node (ref "R45") (pin "2") (pinfunction "2_2") (pintype "passive"))
      (node (ref "R46") (pin "2") (pinfunction "2_2") (pintype "passive"))
      (node (ref "R47") (pin "2") (pinfunction "2_2") (pintype "passive"))
      (node (ref "R56") (pin "2") (pinfunction "2_2") (pintype "passive"))
      (node (ref "R57") (pin "2") (pinfunction "2_2") (pintype "passive"))
      (node (ref "R58") (pin "2") (pinfunction "2_2") (pintype "passive"))
      (node (ref "R59") (pin "2") (pinfunction "2_2") (pintype "passive"))
    )
    (net (code "17") (name "Net-(D1-PadA)") (class "Default")
      (node (ref "D1") (pin "A") (pinfunction "A_A") (pintype "passive"))
      (node (ref "PH1") (pin "1") (pinfunction "1_1") (pintype "passive"))
    )
    (net (code "18") (name "Net-(D2-PadA)") (class "Default")
      (node (ref "D2") (pin "A") (pinfunction "A_A") (pintype "passive"))
      (node (ref "PH2") (pin "1") (pinfunction "1_1") (pintype "passive"))
    )
    (net (code "19") (name "Net-(D3-PadA)") (class "Default")
      (node (ref "D3") (pin "A") (pinfunction "A_A") (pintype "passive"))
      (node (ref "PH3") (pin "1") (pinfunction "1_1") (pintype "passive"))
    )
    (net (code "20") (name "Net-(D4-PadA)") (class "Default")
      (node (ref "D4") (pin "A") (pinfunction "A_A") (pintype "passive"))
      (node (ref "PH4") (pin "1") (pinfunction "1_1") (pintype "passive"))
    )
    (net (code "21") (name "Net-(D5-PadA)") (class "Default")
      (node (ref "D5") (pin "A") (pinfunction "A_A") (pintype "passive"))
      (node (ref "PH5") (pin "1") (pinfunction "1_1") (pintype "passive"))
    )
    (net (code "22") (name "Net-(D6-PadA)") (class "Default")
      (node (ref "D6") (pin "A") (pinfunction "A_A") (pintype "passive"))
      (node (ref "PH6") (pin "1") (pinfunction "1_1") (pintype "passive"))
    )
    (net (code "23") (name "Net-(D7-PadA)") (class "Default")
      (node (ref "D7") (pin "A") (pinfunction "A_A") (pintype "passive"))
      (node (ref "PH7") (pin "1") (pinfunction "1_1") (pintype "passive"))
    )
    (net (code "24") (name "Net-(D8-PadA)") (class "Default")
      (node (ref "D8") (pin "A") (pinfunction "A_A") (pintype "passive"))
      (node (ref "PH8") (pin "1") (pinfunction "1_1") (pintype "passive"))
    )
    (net (code "25") (name "Net-(D9-PadA)") (class "Default")
      (node (ref "D9") (pin "A") (pinfunction "A_A") (pintype "passive"))
      (node (ref "PH9") (pin "1") (pinfunction "1_1") (pintype "passive"))
    )
    (net (code "26") (name "Net-(D10-PadA)") (class "Default")
      (node (ref "D10") (pin "A") (pinfunction "A_A") (pintype "passive"))
      (node (ref "PH10") (pin "1") (pinfunction "1_1") (pintype "passive"))
    )
    (net (code "27") (name "Net-(D11-PadA)") (class "Default")
      (node (ref "D11") (pin "A") (pinfunction "A_A") (pintype "passive"))
      (node (ref "PH11") (pin "1") (pinfunction "1_1") (pintype "passive"))
    )
    (net (code "28") (name "Net-(D12-PadA)") (class "Default")
      (node (ref "D12") (pin "A") (pinfunction "A_A") (pintype "passive"))
      (node (ref "PH12") (pin "1") (pinfunction "1_1") (pintype "passive"))
    )
    (net (code "29") (name "Net-(LED1-C)") (class "Default")
      (node (ref "JR1") (pin "1") (pinfunction "1_1") (pintype "passive"))
      (node (ref "LED1") (pin "K") (pinfunction "C_K") (pintype "passive"))
      (node (ref "LED10") (pin "K") (pinfunction "C_K") (pintype "passive"))
      (node (ref "LED11") (pin "K") (pinfunction "C_K") (pintype "passive"))
      (node (ref "LED12") (pin "K") (pinfunction "C_K") (pintype "passive"))
      (node (ref "LED2") (pin "K") (pinfunction "C_K") (pintype "passive"))
      (node (ref "LED3") (pin "K") (pinfunction "C_K") (pintype "passive"))
      (node (ref "LED4") (pin "K") (pinfunction "C_K") (pintype "passive"))
      (node (ref "LED5") (pin "K") (pinfunction "C_K") (pintype "passive"))
      (node (ref "LED6") (pin "K") (pinfunction "C_K") (pintype "passive"))
      (node (ref "LED7") (pin "K") (pinfunction "C_K") (pintype "passive"))
      (node (ref "LED8") (pin "K") (pinfunction "C_K") (pintype "passive"))
      (node (ref "LED9") (pin "K") (pinfunction "C_K") (pintype "passive"))
      (node (ref "Q1") (pin "3") (pinfunction "C_3") (pintype "passive"))
      (node (ref "ROW1") (pin "1") (pinfunction "1_1") (pintype "passive"))
    )
    (net (code "30") (name "Net-(LED1-PadA)") (class "Default")
      (node (ref "LED1") (pin "A") (pinfunction "A_A") (pintype "passive"))
      (node (ref "R12") (pin "1") (pinfunction "1_1") (pintype "passive"))
    )
    (net (code "31") (name "Net-(LED2-PadA)") (class "Default")
      (node (ref "LED2") (pin "A") (pinfunction "A_A") (pintype "passive"))
      (node (ref "R13") (pin "1") (pinfunction "1_1") (pintype "passive"))
    )
    (net (code "32") (name "Net-(LED3-PadA)") (class "Default")
      (node (ref "LED3") (pin "A") (pinfunction "A_A") (pintype "passive"))
      (node (ref "R14") (pin "1") (pinfunction "1_1") (pintype "passive"))
    )
    (net (code "33") (name "Net-(LED4-PadA)") (class "Default")
      (node (ref "LED4") (pin "A") (pinfunction "A_A") (pintype "passive"))
      (node (ref "R15") (pin "1") (pinfunction "1_1") (pintype "passive"))
    )
    (net (code "34") (name "Net-(LED5-PadA)") (class "Default")
      (node (ref "LED5") (pin "A") (pinfunction "A_A") (pintype "passive"))
      (node (ref "R16") (pin "1") (pinfunction "1_1") (pintype "passive"))
    )
    (net (code "35") (name "Net-(LED6-PadA)") (class "Default")
      (node (ref "LED6") (pin "A") (pinfunction "A_A") (pintype "passive"))
      (node (ref "R17") (pin "1") (pinfunction "1_1") (pintype "passive"))
    )
    (net (code "36") (name "Net-(LED7-PadA)") (class "Default")
      (node (ref "LED7") (pin "A") (pinfunction "A_A") (pintype "passive"))
      (node (ref "R18") (pin "1") (pinfunction "1_1") (pintype "passive"))
    )
    (net (code "37") (name "Net-(LED8-PadA)") (class "Default")
      (node (ref "LED8") (pin "A") (pinfunction "A_A") (pintype "passive"))
      (node (ref "R19") (pin "1") (pinfunction "1_1") (pintype "passive"))
    )
    (net (code "38") (name "Net-(LED9-PadA)") (class "Default")
      (node (ref "LED9") (pin "A") (pinfunction "A_A") (pintype "passive"))
      (node (ref "R20") (pin "1") (pinfunction "1_1") (pintype "passive"))
    )
    (net (code "39") (name "Net-(LED10-PadA)") (class "Default")
      (node (ref "LED10") (pin "A") (pinfunction "A_A") (pintype "passive"))
      (node (ref "R21") (pin "1") (pinfunction "1_1") (pintype "passive"))
    )
    (net (code "40") (name "Net-(LED11-PadA)") (class "Default")
      (node (ref "LED11") (pin "A") (pinfunction "A_A") (pintype "passive"))
      (node (ref "R22") (pin "1") (pinfunction "1_1") (pintype "passive"))
    )
    (net (code "41") (name "Net-(LED12-PadA)") (class "Default")
      (node (ref "LED12") (pin "A") (pinfunction "A_A") (pintype "passive"))
      (node (ref "R23") (pin "1") (pinfunction "1_1") (pintype "passive"))
    )
    (net (code "42") (name "Net-(LED13-C)") (class "Default")
      (node (ref "JR2") (pin "1") (pinfunction "1_1") (pintype "passive"))
      (node (ref "LED13") (pin "K") (pinfunction "C_K") (pintype "passive"))
      (node (ref "LED14") (pin "K") (pinfunction "C_K") (pintype "passive"))
      (node (ref "LED15") (pin "K") (pinfunction "C_K") (pintype "passive"))
      (node (ref "LED16") (pin "K") (pinfunction "C_K") (pintype "passive"))
      (node (ref "LED17") (pin "K") (pinfunction "C_K") (pintype "passive"))
      (node (ref "LED18") (pin "K") (pinfunction "C_K") (pintype "passive"))
      (node (ref "LED19") (pin "K") (pinfunction "C_K") (pintype "passive"))
      (node (ref "LED20") (pin "K") (pinfunction "C_K") (pintype "passive"))
      (node (ref "LED21") (pin "K") (pinfunction "C_K") (pintype "passive"))
      (node (ref "LED22") (pin "K") (pinfunction "C_K") (pintype "passive"))
      (node (ref "LED23") (pin "K") (pinfunction "C_K") (pintype "passive"))
      (node (ref "LED24") (pin "K") (pinfunction "C_K") (pintype "passive"))
      (node (ref "Q2") (pin "3") (pinfunction "C_3") (pintype "passive"))
      (node (ref "ROW2") (pin "1") (pinfunction "1_1") (pintype "passive"))
    )
    (net (code "43") (name "Net-(LED13-PadA)") (class "Default")
      (node (ref "LED13") (pin "A") (pinfunction "A_A") (pintype "passive"))
      (node (ref "R24") (pin "1") (pinfunction "1_1") (pintype "passive"))
    )
    (net (code "44") (name "Net-(LED14-PadA)") (class "Default")
      (node (ref "LED14") (pin "A") (pinfunction "A_A") (pintype "passive"))
      (node (ref "R25") (pin "1") (pinfunction "1_1") (pintype "passive"))
    )
    (net (code "45") (name "Net-(LED15-PadA)") (class "Default")
      (node (ref "LED15") (pin "A") (pinfunction "A_A") (pintype "passive"))
      (node (ref "R26") (pin "1") (pinfunction "1_1") (pintype "passive"))
    )
    (net (code "46") (name "Net-(LED16-PadA)") (class "Default")
      (node (ref "LED16") (pin "A") (pinfunction "A_A") (pintype "passive"))
      (node (ref "R27") (pin "1") (pinfunction "1_1") (pintype "passive"))
    )
    (net (code "47") (name "Net-(LED17-PadA)") (class "Default")
      (node (ref "LED17") (pin "A") (pinfunction "A_A") (pintype "passive"))
      (node (ref "R28") (pin "1") (pinfunction "1_1") (pintype "passive"))
    )
    (net (code "48") (name "Net-(LED18-PadA)") (class "Default")
      (node (ref "LED18") (pin "A") (pinfunction "A_A") (pintype "passive"))
      (node (ref "R29") (pin "1") (pinfunction "1_1") (pintype "passive"))
    )
    (net (code "49") (name "Net-(LED19-PadA)") (class "Default")
      (node (ref "LED19") (pin "A") (pinfunction "A_A") (pintype "passive"))
      (node (ref "R30") (pin "1") (pinfunction "1_1") (pintype "passive"))
    )
    (net (code "50") (name "Net-(LED20-PadA)") (class "Default")
      (node (ref "LED20") (pin "A") (pinfunction "A_A") (pintype "passive"))
      (node (ref "R31") (pin "1") (pinfunction "1_1") (pintype "passive"))
    )
    (net (code "51") (name "Net-(LED21-PadA)") (class "Default")
      (node (ref "LED21") (pin "A") (pinfunction "A_A") (pintype "passive"))
      (node (ref "R32") (pin "1") (pinfunction "1_1") (pintype "passive"))
    )
    (net (code "52") (name "Net-(LED22-PadA)") (class "Default")
      (node (ref "LED22") (pin "A") (pinfunction "A_A") (pintype "passive"))
      (node (ref "R33") (pin "1") (pinfunction "1_1") (pintype "passive"))
    )
    (net (code "53") (name "Net-(LED23-PadA)") (class "Default")
      (node (ref "LED23") (pin "A") (pinfunction "A_A") (pintype "passive"))
      (node (ref "R34") (pin "1") (pinfunction "1_1") (pintype "passive"))
    )
    (net (code "54") (name "Net-(LED24-PadA)") (class "Default")
      (node (ref "LED24") (pin "A") (pinfunction "A_A") (pintype "passive"))
      (node (ref "R35") (pin "1") (pinfunction "1_1") (pintype "passive"))
    )
    (net (code "55") (name "Net-(LED25-C)") (class "Default")
      (node (ref "JR3") (pin "1") (pinfunction "1_1") (pintype "passive"))
      (node (ref "LED25") (pin "K") (pinfunction "C_K") (pintype "passive"))
      (node (ref "LED26") (pin "K") (pinfunction "C_K") (pintype "passive"))
      (node (ref "LED27") (pin "K") (pinfunction "C_K") (pintype "passive"))
      (node (ref "LED28") (pin "K") (pinfunction "C_K") (pintype "passive"))
      (node (ref "LED29") (pin "K") (pinfunction "C_K") (pintype "passive"))
      (node (ref "LED30") (pin "K") (pinfunction "C_K") (pintype "passive"))
      (node (ref "LED31") (pin "K") (pinfunction "C_K") (pintype "passive"))
      (node (ref "LED32") (pin "K") (pinfunction "C_K") (pintype "passive"))
      (node (ref "LED33") (pin "K") (pinfunction "C_K") (pintype "passive"))
      (node (ref "LED34") (pin "K") (pinfunction "C_K") (pintype "passive"))
      (node (ref "LED35") (pin "K") (pinfunction "C_K") (pintype "passive"))
      (node (ref "LED36") (pin "K") (pinfunction "C_K") (pintype "passive"))
      (node (ref "Q3") (pin "3") (pinfunction "C_3") (pintype "passive"))
      (node (ref "ROW3") (pin "1") (pinfunction "1_1") (pintype "passive"))
    )
    (net (code "56") (name "Net-(LED25-PadA)") (class "Default")
      (node (ref "LED25") (pin "A") (pinfunction "A_A") (pintype "passive"))
      (node (ref "R36") (pin "1") (pinfunction "1_1") (pintype "passive"))
    )
    (net (code "57") (name "Net-(LED26-PadA)") (class "Default")
      (node (ref "LED26") (pin "A") (pinfunction "A_A") (pintype "passive"))
      (node (ref "R37") (pin "1") (pinfunction "1_1") (pintype "passive"))
    )
    (net (code "58") (name "Net-(LED27-PadA)") (class "Default")
      (node (ref "LED27") (pin "A") (pinfunction "A_A") (pintype "passive"))
      (node (ref "R38") (pin "1") (pinfunction "1_1") (pintype "passive"))
    )
    (net (code "59") (name "Net-(LED28-PadA)") (class "Default")
      (node (ref "LED28") (pin "A") (pinfunction "A_A") (pintype "passive"))
      (node (ref "R39") (pin "1") (pinfunction "1_1") (pintype "passive"))
    )
    (net (code "60") (name "Net-(LED29-PadA)") (class "Default")
      (node (ref "LED29") (pin "A") (pinfunction "A_A") (pintype "passive"))
      (node (ref "R40") (pin "1") (pinfunction "1_1") (pintype "passive"))
    )
    (net (code "61") (name "Net-(LED30-PadA)") (class "Default")
      (node (ref "LED30") (pin "A") (pinfunction "A_A") (pintype "passive"))
      (node (ref "R41") (pin "1") (pinfunction "1_1") (pintype "passive"))
    )
    (net (code "62") (name "Net-(LED31-PadA)") (class "Default")
      (node (ref "LED31") (pin "A") (pinfunction "A_A") (pintype "passive"))
      (node (ref "R42") (pin "1") (pinfunction "1_1") (pintype "passive"))
    )
    (net (code "63") (name "Net-(LED32-PadA)") (class "Default")
      (node (ref "LED32") (pin "A") (pinfunction "A_A") (pintype "passive"))
      (node (ref "R43") (pin "1") (pinfunction "1_1") (pintype "passive"))
    )
    (net (code "64") (name "Net-(LED33-PadA)") (class "Default")
      (node (ref "LED33") (pin "A") (pinfunction "A_A") (pintype "passive"))
      (node (ref "R44") (pin "1") (pinfunction "1_1") (pintype "passive"))
    )
    (net (code "65") (name "Net-(LED34-PadA)") (class "Default")
      (node (ref "LED34") (pin "A") (pinfunction "A_A") (pintype "passive"))
      (node (ref "R45") (pin "1") (pinfunction "1_1") (pintype "passive"))
    )
    (net (code "66") (name "Net-(LED35-PadA)") (class "Default")
      (node (ref "LED35") (pin "A") (pinfunction "A_A") (pintype "passive"))
      (node (ref "R46") (pin "1") (pinfunction "1_1") (pintype "passive"))
    )
    (net (code "67") (name "Net-(LED36-PadA)") (class "Default")
      (node (ref "LED36") (pin "A") (pinfunction "A_A") (pintype "passive"))
      (node (ref "R47") (pin "1") (pinfunction "1_1") (pintype "passive"))
    )
    (net (code "68") (name "Net-(LED37-C)") (class "Default")
      (node (ref "JR4") (pin "1") (pinfunction "1_1") (pintype "passive"))
      (node (ref "LED37") (pin "K") (pinfunction "C_K") (pintype "passive"))
      (node (ref "LED38") (pin "K") (pinfunction "C_K") (pintype "passive"))
      (node (ref "LED39") (pin "K") (pinfunction "C_K") (pintype "passive"))
      (node (ref "LED40") (pin "K") (pinfunction "C_K") (pintype "passive"))
      (node (ref "LED41") (pin "K") (pinfunction "C_K") (pintype "passive"))
      (node (ref "LED42") (pin "K") (pinfunction "C_K") (pintype "passive"))
      (node (ref "LED43") (pin "K") (pinfunction "C_K") (pintype "passive"))
      (node (ref "LED44") (pin "K") (pinfunction "C_K") (pintype "passive"))
      (node (ref "LED45") (pin "K") (pinfunction "C_K") (pintype "passive"))
      (node (ref "LED46") (pin "K") (pinfunction "C_K") (pintype "passive"))
      (node (ref "LED47") (pin "K") (pinfunction "C_K") (pintype "passive"))
      (node (ref "LED48") (pin "K") (pinfunction "C_K") (pintype "passive"))
      (node (ref "Q4") (pin "3") (pinfunction "C_3") (pintype "passive"))
      (node (ref "ROW4") (pin "1") (pinfunction "1_1") (pintype "passive"))
    )
    (net (code "69") (name "Net-(LED37-PadA)") (class "Default")
      (node (ref "LED37") (pin "A") (pinfunction "A_A") (pintype "passive"))
      (node (ref "R48") (pin "1") (pinfunction "1_1") (pintype "passive"))
    )
    (net (code "70") (name "Net-(LED38-PadA)") (class "Default")
      (node (ref "LED38") (pin "A") (pinfunction "A_A") (pintype "passive"))
      (node (ref "R49") (pin "1") (pinfunction "1_1") (pintype "passive"))
    )
    (net (code "71") (name "Net-(LED39-PadA)") (class "Default")
      (node (ref "LED39") (pin "A") (pinfunction "A_A") (pintype "passive"))
      (node (ref "R50") (pin "1") (pinfunction "1_1") (pintype "passive"))
    )
    (net (code "72") (name "Net-(LED40-PadA)") (class "Default")
      (node (ref "LED40") (pin "A") (pinfunction "A_A") (pintype "passive"))
      (node (ref "R51") (pin "1") (pinfunction "1_1") (pintype "passive"))
    )
    (net (code "73") (name "Net-(LED41-PadA)") (class "Default")
      (node (ref "LED41") (pin "A") (pinfunction "A_A") (pintype "passive"))
      (node (ref "R52") (pin "1") (pinfunction "1_1") (pintype "passive"))
    )
    (net (code "74") (name "Net-(LED42-PadA)") (class "Default")
      (node (ref "LED42") (pin "A") (pinfunction "A_A") (pintype "passive"))
      (node (ref "R53") (pin "1") (pinfunction "1_1") (pintype "passive"))
    )
    (net (code "75") (name "Net-(LED43-PadA)") (class "Default")
      (node (ref "LED43") (pin "A") (pinfunction "A_A") (pintype "passive"))
      (node (ref "R54") (pin "1") (pinfunction "1_1") (pintype "passive"))
    )
    (net (code "76") (name "Net-(LED44-PadA)") (class "Default")
      (node (ref "LED44") (pin "A") (pinfunction "A_A") (pintype "passive"))
      (node (ref "R55") (pin "1") (pinfunction "1_1") (pintype "passive"))
    )
    (net (code "77") (name "Net-(LED45-PadA)") (class "Default")
      (node (ref "LED45") (pin "A") (pinfunction "A_A") (pintype "passive"))
      (node (ref "R56") (pin "1") (pinfunction "1_1") (pintype "passive"))
    )
    (net (code "78") (name "Net-(LED46-PadA)") (class "Default")
      (node (ref "LED46") (pin "A") (pinfunction "A_A") (pintype "passive"))
      (node (ref "R57") (pin "1") (pinfunction "1_1") (pintype "passive"))
    )
    (net (code "79") (name "Net-(LED47-PadA)") (class "Default")
      (node (ref "LED47") (pin "A") (pinfunction "A_A") (pintype "passive"))
      (node (ref "R58") (pin "1") (pinfunction "1_1") (pintype "passive"))
    )
    (net (code "80") (name "Net-(LED48-PadA)") (class "Default")
      (node (ref "LED48") (pin "A") (pinfunction "A_A") (pintype "passive"))
      (node (ref "R59") (pin "1") (pinfunction "1_1") (pintype "passive"))
    )
    (net (code "81") (name "Net-(Q1-B)") (class "Default")
      (node (ref "Q1") (pin "1") (pinfunction "B_1") (pintype "passive"))
      (node (ref "R5") (pin "2") (pinfunction "2_2") (pintype "passive"))
    )
    (net (code "82") (name "Net-(Q2-B)") (class "Default")
      (node (ref "Q2") (pin "1") (pinfunction "B_1") (pintype "passive"))
      (node (ref "R6") (pin "2") (pinfunction "2_2") (pintype "passive"))
    )
    (net (code "83") (name "Net-(Q3-B)") (class "Default")
      (node (ref "Q3") (pin "1") (pinfunction "B_1") (pintype "passive"))
      (node (ref "R7") (pin "2") (pinfunction "2_2") (pintype "passive"))
    )
    (net (code "84") (name "Net-(Q4-B)") (class "Default")
      (node (ref "Q4") (pin "1") (pinfunction "B_1") (pintype "passive"))
      (node (ref "R8") (pin "2") (pinfunction "2_2") (pintype "passive"))
    )
    (net (code "85") (name "Net-(Q5-PadB)") (class "Default")
      (node (ref "Q5") (pin "B") (pinfunction "B_B") (pintype "passive"))
      (node (ref "R9") (pin "1") (pinfunction "1_1") (pintype "passive"))
    )
    (net (code "86") (name "Net-(Q6-PadB)") (class "Default")
      (node (ref "Q6") (pin "B") (pinfunction "B_B") (pintype "passive"))
      (node (ref "R10") (pin "1") (pinfunction "1_1") (pintype "passive"))
    )
    (net (code "87") (name "Net-(Q7-PadB)") (class "Default")
      (node (ref "Q7") (pin "B") (pinfunction "B_B") (pintype "passive"))
      (node (ref "R11") (pin "1") (pinfunction "1_1") (pintype "passive"))
    )
  )
)
